# DT01_ID.net
KiCad netlist of a schematic drawn in Altium Designer
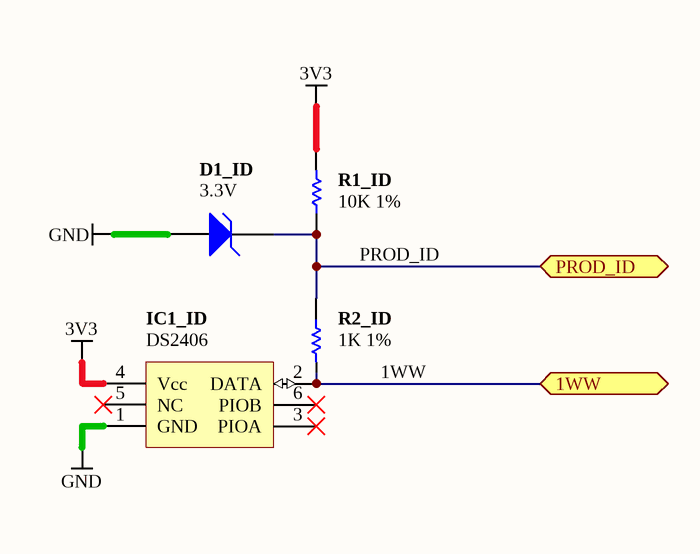
[diagram p0: DT01_ID.SchDoc]

(export (version "E")
  (design (tool "Eeschema 10.0.6"))
  (components
    (comp (ref "D1_ID")
      (value "3.3V")
      (footprint "SOT95P230-3D")
      (description "Zener Diode, 3.3V")
      (libsource (lib "AltiumDesignLibrary") (part "DIO-ZENER-1-3"))
    )
    (comp (ref "IC1_ID")
      (value "DS2406")
      (footprint "TSOC6")
      (description "Dual Addressable Switch Plus 1KB Memory")
      (libsource (lib "AltiumDesignLibrary") (part "DS2406"))
    )
    (comp (ref "R1_ID")
      (value "10K 1%")
      (footprint "RESC1005-STAR")
      (description "Resistor, 10K 1% 0402 (1005)")
      (fields (field (name "TOLERANCE") "1 %"))
      (libsource (lib "AltiumDesignLibrary") (part "RES"))
    )
    (comp (ref "R2_ID")
      (value "1K 1%")
      (footprint "RESC1005-STAR")
      (description "Resistor, 1K 1% 0402 (1005)")
      (fields (field (name "TOLERANCE") "1 %"))
      (libsource (lib "AltiumDesignLibrary") (part "RES"))
    )
  )
  (nets
    (net (code "1") (name "/1WW") (class "Default")
      (node (ref "IC1_ID") (pin "2") (pinfunction "DATA_2") (pintype "bidirectional"))
      (node (ref "R2_ID") (pin "2") (pinfunction "2_2") (pintype "passive"))
    )
    (net (code "2") (name "/PROD_ID") (class "Default")
      (node (ref "D1_ID") (pin "2") (pinfunction "K_2") (pintype "passive"))
      (node (ref "R1_ID") (pin "1") (pinfunction "1_1") (pintype "passive"))
      (node (ref "R2_ID") (pin "1") (pinfunction "1_1") (pintype "passive"))
    )
    (net (code "3") (name "3V3") (class "Default")
      (node (ref "IC1_ID") (pin "4") (pinfunction "Vcc_4") (pintype "passive"))
      (node (ref "R1_ID") (pin "2") (pinfunction "2_2") (pintype "passive"))
    )
    (net (code "4") (name "GND") (class "Default")
      (node (ref "D1_ID") (pin "1") (pinfunction "A_1") (pintype "passive"))
      (node (ref "IC1_ID") (pin "1") (pinfunction "GND_1") (pintype "power_in"))
    )
    (net (code "5") (name "unconnected-(IC1_ID-NC-Pad5)") (class "Default")
      (node (ref "IC1_ID") (pin "5") (pinfunction "NC_5") (pintype "passive+no_connect"))
    )
    (net (code "6") (name "unconnected-(IC1_ID-PIOA-Pad3)") (class "Default")
      (node (ref "IC1_ID") (pin "3") (pinfunction "PIOA_3") (pintype "open_collector+no_connect"))
    )
    (net (code "7") (name "unconnected-(IC1_ID-PIOB-Pad6)") (class "Default")
      (node (ref "IC1_ID") (pin "6") (pinfunction "PIOB_6") (pintype "passive+no_connect"))
    )
  )
)
